# PiPod_Rev3.net
KiCad netlist of a schematic drawn in EAGLE
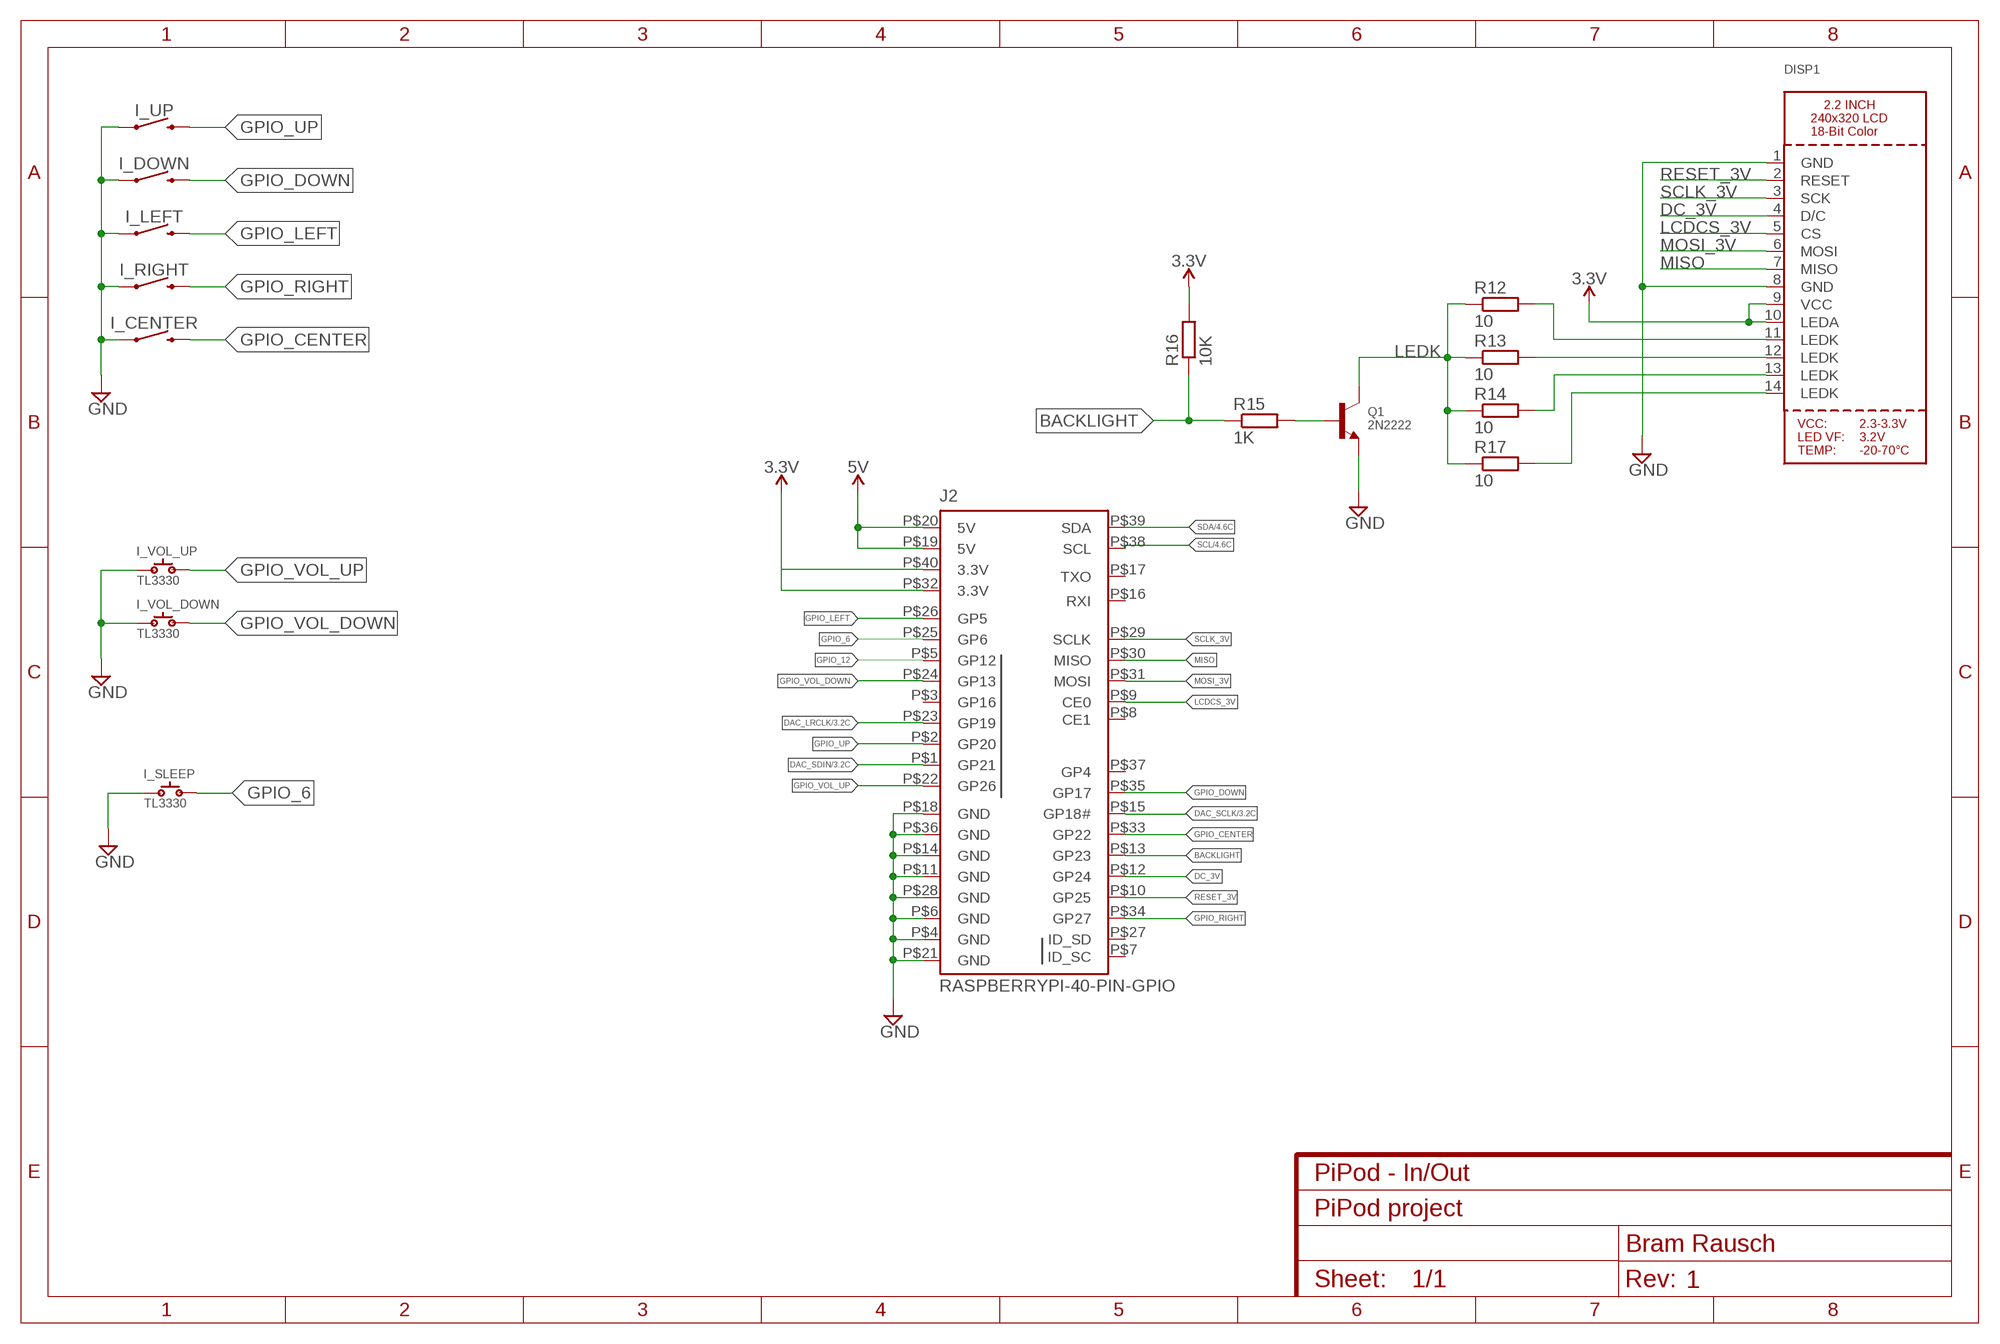
[diagram p0: schematic, sheet 1]
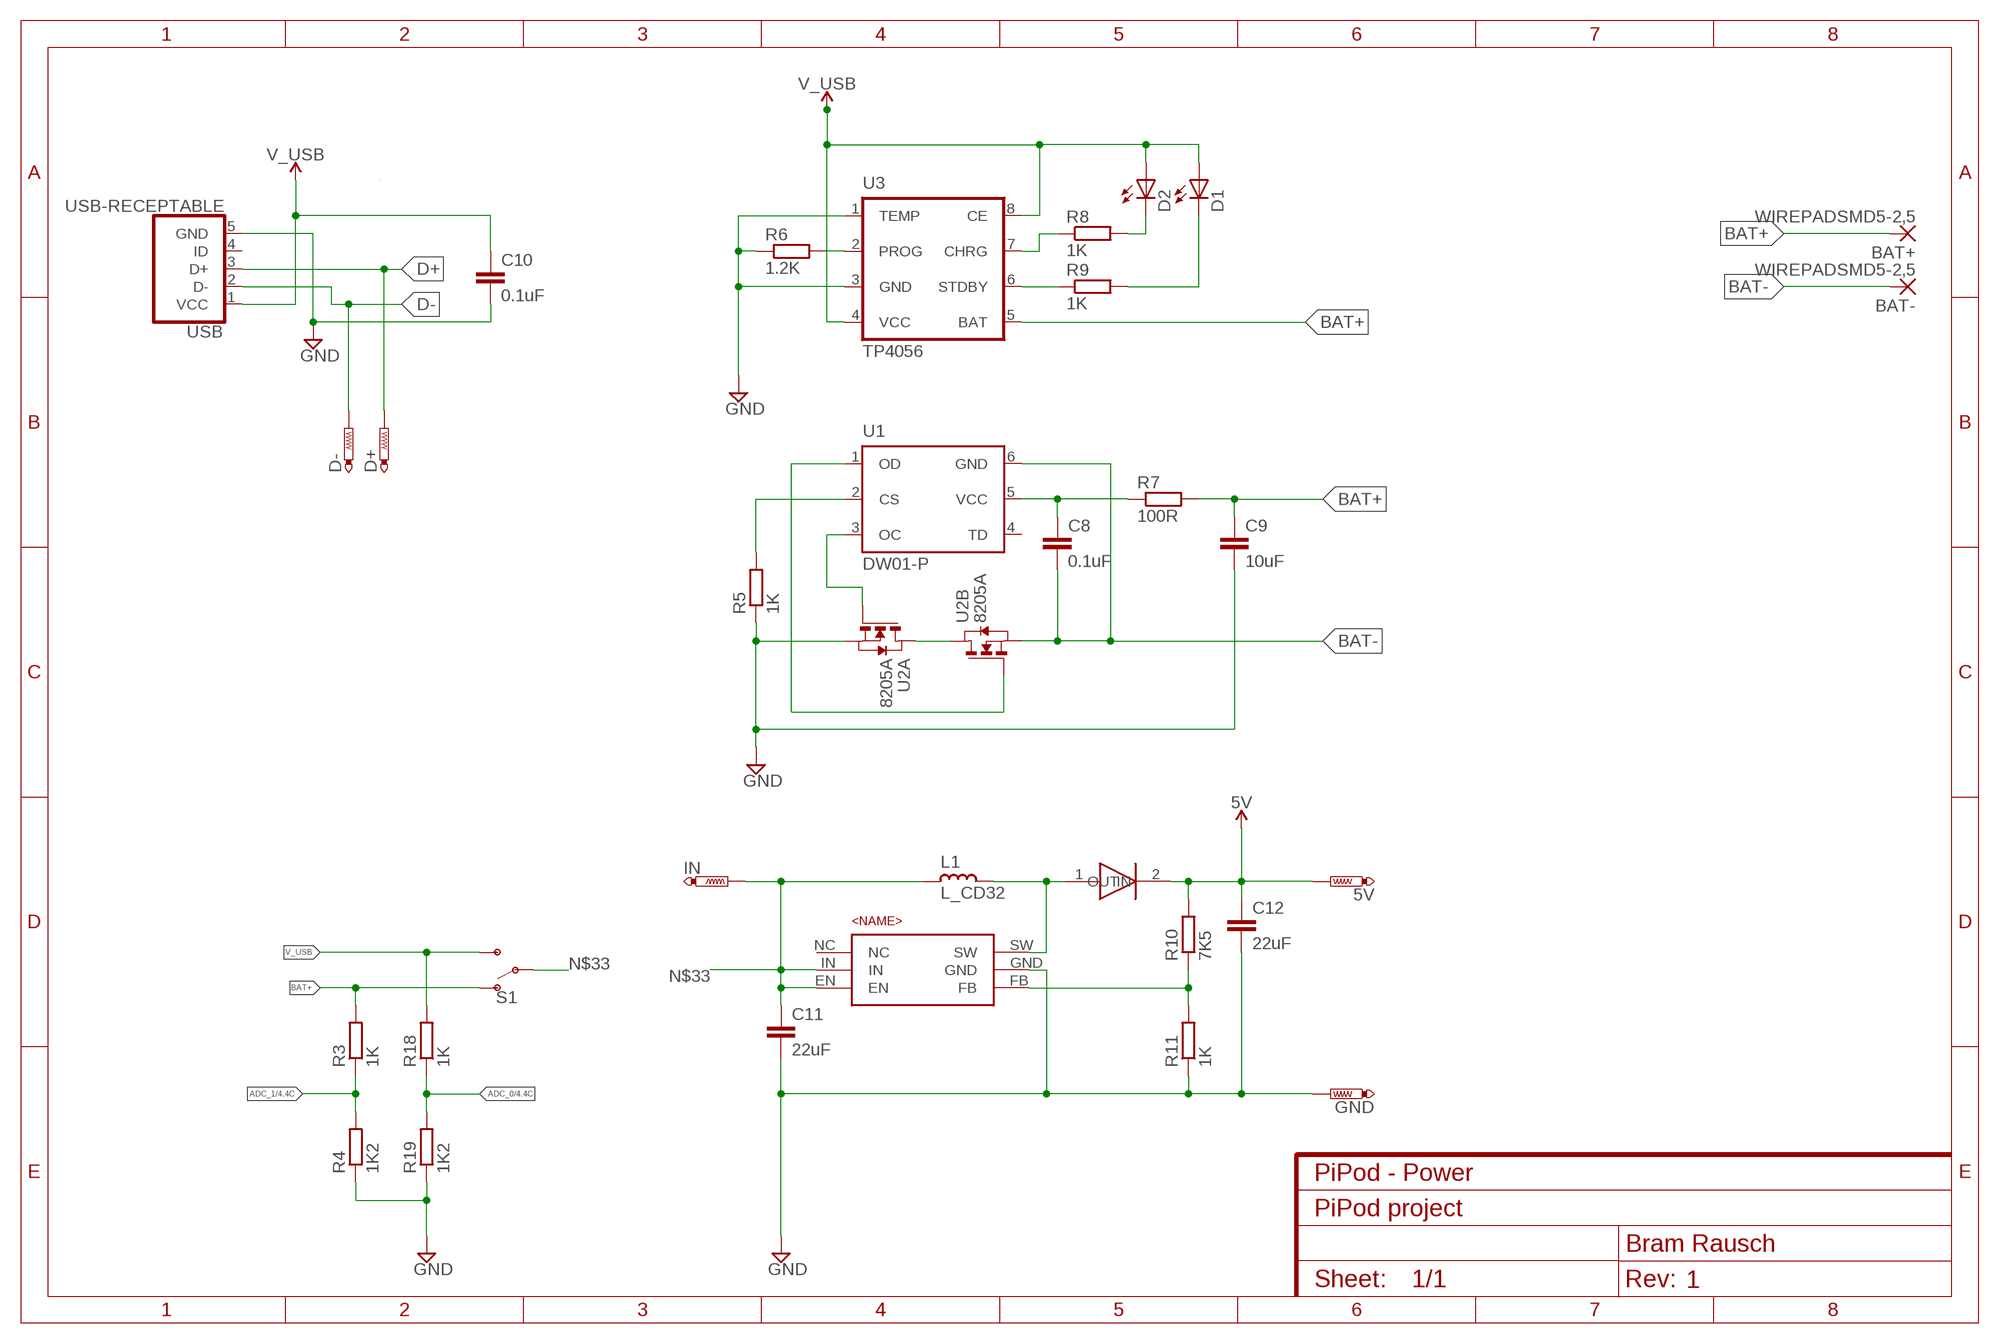
[diagram p1: schematic, sheet 2]
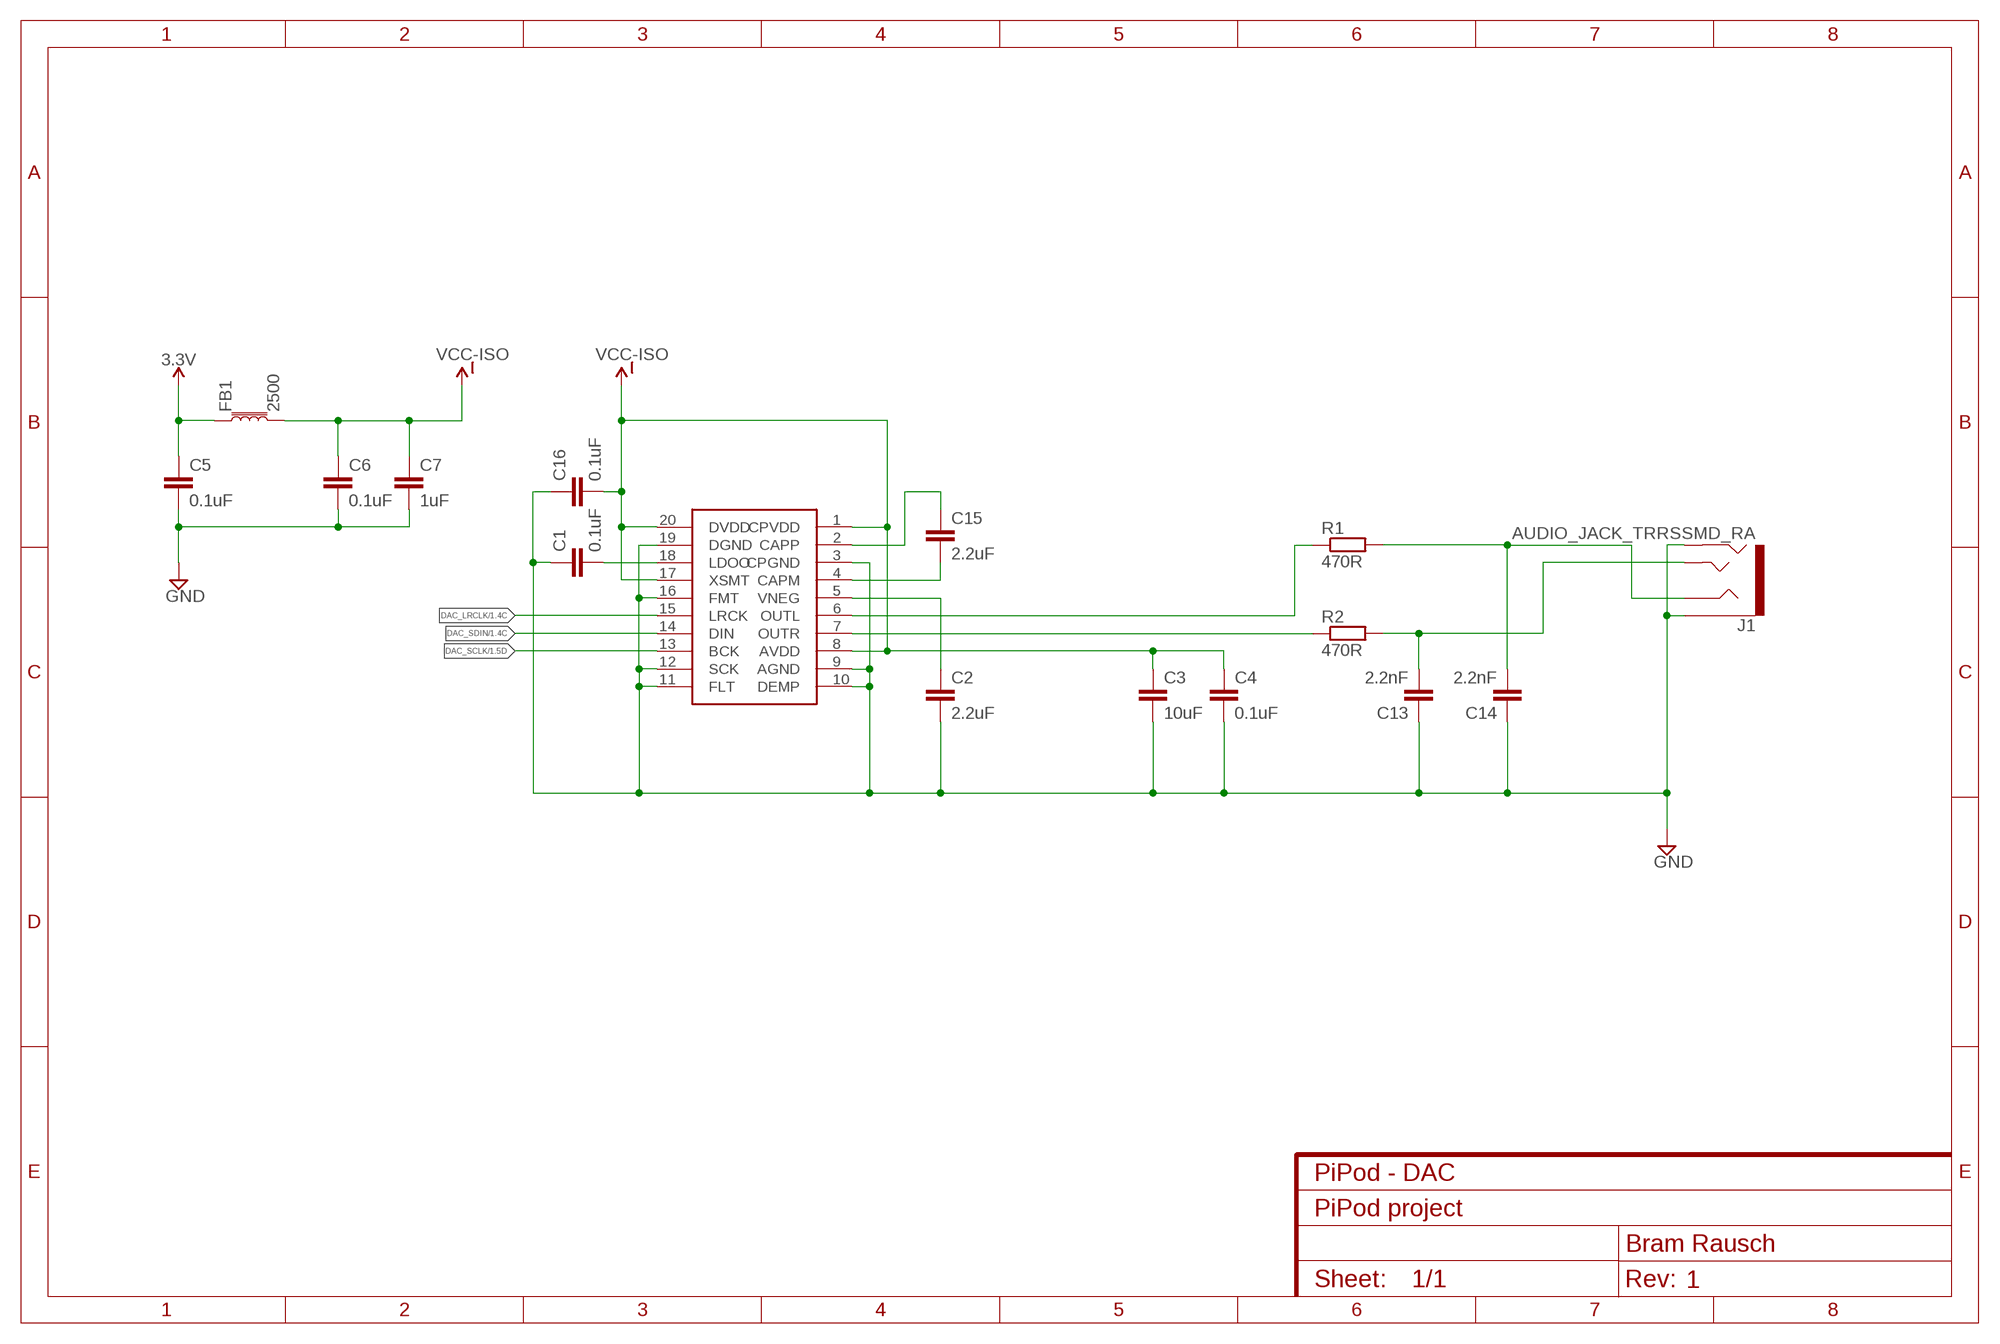
[diagram p2: schematic, sheet 3]
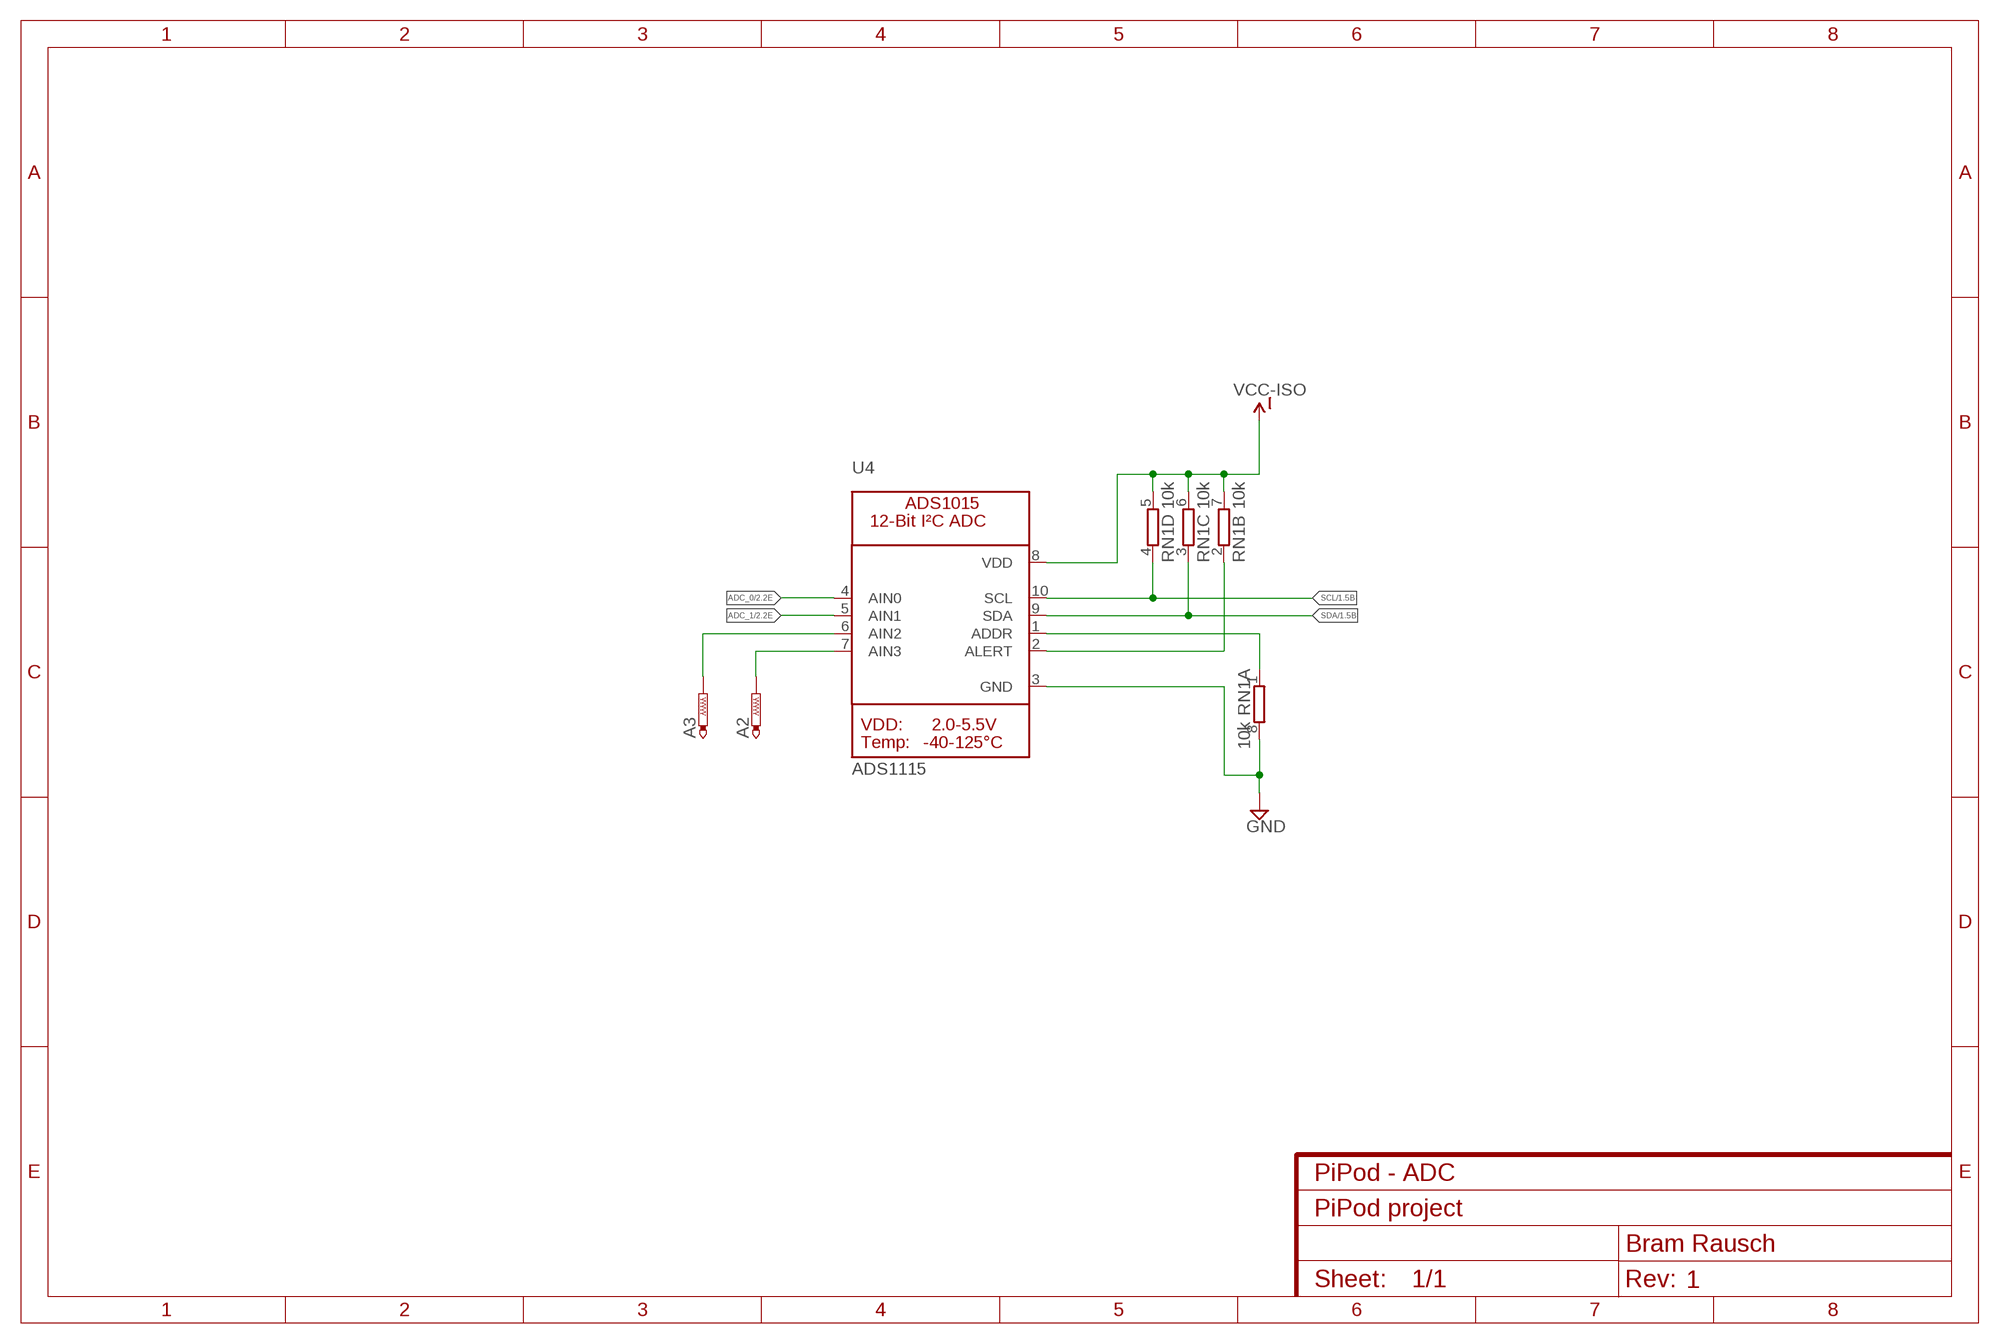
[diagram p3: schematic, sheet 4]

(export (version "E")
  (design (tool "Eeschema 10.0.6"))
  (components
    (comp (ref "DISP1")
      (value "DISP_LCD_TM022HDH26")
      (footprint "eagle-import:TM022HDH26_2.2IN_LCD")
      (libsource (lib "eagle-import") (part "DISP_LCD_TM022HDH26"))
    )
    (comp (ref "I_CENTER")
      (value "MOMENTARY-SWITCH-SPST-SMD-5.2-REDUNDANT")
      (footprint "eagle-import:TACTILE_SWITCH_SMD_5.2MM")
      (libsource (lib "eagle-import") (part "MOMENTARY-SWITCH-SPST-SMD-5.2-REDUNDANT"))
    )
    (comp (ref "I_DOWN")
      (value "MOMENTARY-SWITCH-SPST-SMD-5.2-REDUNDANT")
      (footprint "eagle-import:TACTILE_SWITCH_SMD_5.2MM")
      (libsource (lib "eagle-import") (part "MOMENTARY-SWITCH-SPST-SMD-5.2-REDUNDANT"))
    )
    (comp (ref "I_LEFT")
      (value "MOMENTARY-SWITCH-SPST-SMD-5.2-REDUNDANT")
      (footprint "eagle-import:TACTILE_SWITCH_SMD_5.2MM")
      (libsource (lib "eagle-import") (part "MOMENTARY-SWITCH-SPST-SMD-5.2-REDUNDANT"))
    )
    (comp (ref "I_RIGHT")
      (value "MOMENTARY-SWITCH-SPST-SMD-5.2-REDUNDANT")
      (footprint "eagle-import:TACTILE_SWITCH_SMD_5.2MM")
      (libsource (lib "eagle-import") (part "MOMENTARY-SWITCH-SPST-SMD-5.2-REDUNDANT"))
    )
    (comp (ref "I_SLEEP")
      (value "TL3330")
      (footprint "eagle-import:TL3330")
      (libsource (lib "eagle-import") (part "TL3330"))
    )
    (comp (ref "I_UP")
      (value "MOMENTARY-SWITCH-SPST-SMD-5.2-REDUNDANT")
      (footprint "eagle-import:TACTILE_SWITCH_SMD_5.2MM")
      (libsource (lib "eagle-import") (part "MOMENTARY-SWITCH-SPST-SMD-5.2-REDUNDANT"))
    )
    (comp (ref "I_VOL_DOWN")
      (value "TL3330")
      (footprint "eagle-import:TL3330")
      (libsource (lib "eagle-import") (part "TL3330"))
    )
    (comp (ref "I_VOL_UP")
      (value "TL3330")
      (footprint "eagle-import:TL3330")
      (libsource (lib "eagle-import") (part "TL3330"))
    )
    (comp (ref "J2")
      (value "RASPBERRYPI-40-PIN-GPIO")
      (footprint "eagle-import:2X20_SMD")
      (libsource (lib "eagle-import") (part "RASPBERRYPI-40-PIN-GPIO"))
    )
    (comp (ref "Q1")
      (value "2N2222")
      (footprint "eagle-import:SOT23-WIDE")
      (libsource (lib "eagle-import") (part "TRANSISTOR_NPNWIDE"))
    )
    (comp (ref "R12")
      (value "10")
      (footprint "eagle-import:R0805")
      (libsource (lib "eagle-import") (part "R-EU_R0805"))
    )
    (comp (ref "R13")
      (value "10")
      (footprint "eagle-import:R0805")
      (libsource (lib "eagle-import") (part "R-EU_R0805"))
    )
    (comp (ref "R14")
      (value "10")
      (footprint "eagle-import:R0805")
      (libsource (lib "eagle-import") (part "R-EU_R0805"))
    )
    (comp (ref "R15")
      (value "1K")
      (footprint "eagle-import:R0805")
      (libsource (lib "eagle-import") (part "R-EU_R0805"))
    )
    (comp (ref "R16")
      (value "10K")
      (footprint "eagle-import:R0805")
      (libsource (lib "eagle-import") (part "R-EU_R0805"))
    )
    (comp (ref "R17")
      (value "10")
      (footprint "eagle-import:R0805")
      (libsource (lib "eagle-import") (part "R-EU_R0805"))
    )
    (comp (ref "C1")
      (value "0.1uF")
      (footprint "eagle-import:C0805K")
      (libsource (lib "eagle-import") (part "C-EUC0805K"))
    )
    (comp (ref "C2")
      (value "2.2uF")
      (footprint "eagle-import:C0805K")
      (libsource (lib "eagle-import") (part "C-EUC0805K"))
    )
    (comp (ref "C3")
      (value "10uF")
      (footprint "eagle-import:C0805K")
      (libsource (lib "eagle-import") (part "C-EUC0805K"))
    )
    (comp (ref "C4")
      (value "0.1uF")
      (footprint "eagle-import:C0805K")
      (libsource (lib "eagle-import") (part "C-EUC0805K"))
    )
    (comp (ref "C5")
      (value "0.1uF")
      (footprint "eagle-import:C0805K")
      (libsource (lib "eagle-import") (part "C-EUC0805K"))
    )
    (comp (ref "C6")
      (value "0.1uF")
      (footprint "eagle-import:C0805K")
      (libsource (lib "eagle-import") (part "C-EUC0805K"))
    )
    (comp (ref "C7")
      (value "1uF")
      (footprint "eagle-import:C0805K")
      (libsource (lib "eagle-import") (part "C-EUC0805K"))
    )
    (comp (ref "C13")
      (value "2.2nF")
      (footprint "eagle-import:C0805K")
      (libsource (lib "eagle-import") (part "C-EUC0805K"))
    )
    (comp (ref "C14")
      (value "2.2nF")
      (footprint "eagle-import:C0805K")
      (libsource (lib "eagle-import") (part "C-EUC0805K"))
    )
    (comp (ref "C15")
      (value "2.2uF")
      (footprint "eagle-import:C0805K")
      (libsource (lib "eagle-import") (part "C-EUC0805K"))
    )
    (comp (ref "C16")
      (value "0.1uF")
      (footprint "eagle-import:C0805K")
      (libsource (lib "eagle-import") (part "C-EUC0805K"))
    )
    (comp (ref "FB1")
      (value "2500")
      (footprint "eagle-import:0603")
      (libsource (lib "eagle-import") (part "FERRITE_BEAD-0603"))
    )
    (comp (ref "J1")
      (value "AUDIO_JACK_TRRSSMD_RA")
      (footprint "eagle-import:AUDIO_JACK_3.5MM_TRRS_SMD_RA")
      (libsource (lib "eagle-import") (part "AUDIO_JACK_TRRSSMD_RA"))
    )
    (comp (ref "R1")
      (value "470R")
      (footprint "eagle-import:R0805")
      (libsource (lib "eagle-import") (part "R-EU_R0805"))
    )
    (comp (ref "R2")
      (value "470R")
      (footprint "eagle-import:R0805")
      (libsource (lib "eagle-import") (part "R-EU_R0805"))
    )
    (comp (ref "U5")
      (value "PCM5102")
      (footprint "eagle-import:TSSOP20")
      (libsource (lib "eagle-import") (part "PCM5102"))
    )
    (comp (ref "5V")
      (value "PTR1B2,54")
      (footprint "eagle-import:B2,54")
      (libsource (lib "eagle-import") (part "PTR1B2,54"))
    )
    (comp (ref "BAT+")
      (value "WIREPADSMD5-2,5")
      (footprint "eagle-import:5-2,5")
      (libsource (lib "eagle-import") (part "WIREPADSMD5-2,5"))
    )
    (comp (ref "BAT-")
      (value "WIREPADSMD5-2,5")
      (footprint "eagle-import:5-2,5")
      (libsource (lib "eagle-import") (part "WIREPADSMD5-2,5"))
    )
    (comp (ref "C8")
      (value "0.1uF")
      (footprint "eagle-import:C1206K")
      (libsource (lib "eagle-import") (part "resistor_348_C-EUC1206K"))
    )
    (comp (ref "C9")
      (value "10uF")
      (footprint "eagle-import:C1206K")
      (libsource (lib "eagle-import") (part "resistor_348_C-EUC1206K"))
    )
    (comp (ref "C10")
      (value "0.1uF")
      (footprint "eagle-import:C1206K")
      (libsource (lib "eagle-import") (part "resistor_348_C-EUC1206K"))
    )
    (comp (ref "C11")
      (value "22uF")
      (footprint "eagle-import:C0805K")
      (libsource (lib "eagle-import") (part "resistor_348_C-EUC0805K"))
    )
    (comp (ref "C12")
      (value "22uF")
      (footprint "eagle-import:C0805K")
      (libsource (lib "eagle-import") (part "resistor_348_C-EUC0805K"))
    )
    (comp (ref "D+")
      (value "PTR1TP15R")
      (footprint "eagle-import:TP15R")
      (libsource (lib "eagle-import") (part "PTR1TP15R"))
    )
    (comp (ref "D-")
      (value "PTR1TP15R")
      (footprint "eagle-import:TP15R")
      (libsource (lib "eagle-import") (part "PTR1TP15R"))
    )
    (comp (ref "D1")
      (value "LEDCHIPLED_0805")
      (footprint "eagle-import:CHIPLED_0805")
      (libsource (lib "eagle-import") (part "LEDCHIPLED_0805"))
    )
    (comp (ref "D2")
      (value "LEDCHIPLED_0805")
      (footprint "eagle-import:CHIPLED_0805")
      (libsource (lib "eagle-import") (part "LEDCHIPLED_0805"))
    )
    (comp (ref "GND")
      (value "PTR1B2,54")
      (footprint "eagle-import:B2,54")
      (libsource (lib "eagle-import") (part "PTR1B2,54"))
    )
    (comp (ref "IN")
      (value "PTR1B2,54")
      (footprint "eagle-import:B2,54")
      (libsource (lib "eagle-import") (part "PTR1B2,54"))
    )
    (comp (ref "L1")
      (value "L_CD32")
      (footprint "eagle-import:CD32")
      (libsource (lib "eagle-import") (part "L_CD32"))
    )
    (comp (ref "R3")
      (value "1K")
      (footprint "eagle-import:R0805")
      (libsource (lib "eagle-import") (part "R-EU_R0805"))
    )
    (comp (ref "R4")
      (value "1K2")
      (footprint "eagle-import:R0805")
      (libsource (lib "eagle-import") (part "R-EU_R0805"))
    )
    (comp (ref "R5")
      (value "1K")
      (footprint "eagle-import:M0805")
      (libsource (lib "eagle-import") (part "R-EU_M0805"))
    )
    (comp (ref "R6")
      (value "1.2K")
      (footprint "eagle-import:M0805")
      (libsource (lib "eagle-import") (part "R-EU_M0805"))
    )
    (comp (ref "R7")
      (value "100R")
      (footprint "eagle-import:M0805")
      (libsource (lib "eagle-import") (part "R-EU_M0805"))
    )
    (comp (ref "R8")
      (value "1K")
      (footprint "eagle-import:M0805")
      (libsource (lib "eagle-import") (part "R-EU_M0805"))
    )
    (comp (ref "R9")
      (value "1K")
      (footprint "eagle-import:M0805")
      (libsource (lib "eagle-import") (part "R-EU_M0805"))
    )
    (comp (ref "R10")
      (value "7K5")
      (footprint "eagle-import:R0805")
      (libsource (lib "eagle-import") (part "R-EU_R0805"))
    )
    (comp (ref "R11")
      (value "1K")
      (footprint "eagle-import:R0805")
      (libsource (lib "eagle-import") (part "R-EU_R0805"))
    )
    (comp (ref "R18")
      (value "1K")
      (footprint "eagle-import:R0805")
      (libsource (lib "eagle-import") (part "R-EU_R0805"))
    )
    (comp (ref "R19")
      (value "1K2")
      (footprint "eagle-import:R0805")
      (libsource (lib "eagle-import") (part "R-EU_R0805"))
    )
    (comp (ref "S1")
      (value "SWITCH-SPDT-PTH-11.6X4.0MM")
      (footprint "eagle-import:SWITCH_SPDT_PTH_11.6X4.0MM")
      (libsource (lib "eagle-import") (part "SWITCH-SPDT-PTH-11.6X4.0MM"))
    )
    (comp (ref "U$9")
      (value "SMA-SS34")
      (footprint "eagle-import:SMA-SS34")
      (libsource (lib "eagle-import") (part "SMA-SS34"))
    )
    (comp (ref "U1")
      (value "DW01-P")
      (footprint "eagle-import:SOT23-6L")
      (libsource (lib "eagle-import") (part "DW01-P"))
    )
    (comp (ref "U2")
      (value "8205A")
      (footprint "eagle-import:TSSOP8")
      (libsource (lib "eagle-import") (part "8205A"))
    )
    (comp (ref "U3")
      (value "TP4056")
      (footprint "eagle-import:SO08")
      (libsource (lib "eagle-import") (part "TP4056"))
    )
    (comp (ref "U6")
      (value "MT3608")
      (footprint "eagle-import:SOT23-6")
      (libsource (lib "eagle-import") (part "MT3608"))
    )
    (comp (ref "USB")
      (value "USB-RECEPTABLE")
      (footprint "eagle-import:FCI-10103594-0001LF")
      (libsource (lib "eagle-import") (part "USB-RECEPTABLE"))
    )
    (comp (ref "A2")
      (value "PTR1TP15R")
      (footprint "eagle-import:TP15R")
      (libsource (lib "eagle-import") (part "PTR1TP15R"))
    )
    (comp (ref "A3")
      (value "PTR1TP15R")
      (footprint "eagle-import:TP15R")
      (libsource (lib "eagle-import") (part "PTR1TP15R"))
    )
    (comp (ref "RN1")
      (value "10k")
      (footprint "eagle-import:0603-ARC")
      (libsource (lib "eagle-import") (part "4R-N0603-ARC"))
    )
    (comp (ref "U4")
      (value "ADS1115")
      (footprint "eagle-import:MICROBUILDER_MSOP10")
      (libsource (lib "eagle-import") (part "MICROBUILDER_ADC_ADS1015"))
    )
  )
  (nets
    (net (code "1") (name "3.3V") (class "Default")
      (node (ref "C5") (pin "1") (pinfunction "1_1") (pintype "passive"))
      (node (ref "DISP1") (pin "10") (pinfunction "LEDA_10") (pintype "power_in"))
      (node (ref "DISP1") (pin "9") (pinfunction "VCC_9") (pintype "power_in"))
      (node (ref "FB1") (pin "1") (pinfunction "1_1") (pintype "passive"))
      (node (ref "J2") (pin "P$32") (pinfunction "3.3V_P$32") (pintype "power_in"))
      (node (ref "J2") (pin "P$40") (pinfunction "3.3V_P$40") (pintype "power_in"))
      (node (ref "R16") (pin "2") (pinfunction "2_2") (pintype "passive"))
    )
    (net (code "2") (name "5V") (class "Default")
      (node (ref "5V") (pin "TP") (pinfunction "TP_TP") (pintype "input"))
      (node (ref "C12") (pin "1") (pinfunction "1_1") (pintype "passive"))
      (node (ref "J2") (pin "P$19") (pinfunction "5V_P$19") (pintype "power_in"))
      (node (ref "J2") (pin "P$20") (pinfunction "5V_P$20") (pintype "power_in"))
      (node (ref "R10") (pin "2") (pinfunction "2_2") (pintype "passive"))
      (node (ref "U$9") (pin "2") (pinfunction "OUT_2") (pintype "bidirectional"))
    )
    (net (code "3") (name "ADC_0") (class "Default")
      (node (ref "R18") (pin "1") (pinfunction "1_1") (pintype "passive"))
      (node (ref "R19") (pin "2") (pinfunction "2_2") (pintype "passive"))
      (node (ref "U4") (pin "4") (pinfunction "AIN0_4") (pintype "bidirectional"))
    )
    (net (code "4") (name "ADC_1") (class "Default")
      (node (ref "R3") (pin "1") (pinfunction "1_1") (pintype "passive"))
      (node (ref "R4") (pin "2") (pinfunction "2_2") (pintype "passive"))
      (node (ref "U4") (pin "5") (pinfunction "AIN1_5") (pintype "bidirectional"))
    )
    (net (code "5") (name "BACKLIGHT") (class "Default")
      (node (ref "J2") (pin "P$13") (pinfunction "GP23_P$13") (pintype "bidirectional"))
      (node (ref "R15") (pin "1") (pinfunction "1_1") (pintype "passive"))
      (node (ref "R16") (pin "1") (pinfunction "1_1") (pintype "passive"))
    )
    (net (code "6") (name "BAT+") (class "Default")
      (node (ref "BAT+") (pin "1") (pinfunction "P_1") (pintype "passive"))
      (node (ref "C9") (pin "1") (pinfunction "1_1") (pintype "passive"))
      (node (ref "R3") (pin "2") (pinfunction "2_2") (pintype "passive"))
      (node (ref "R7") (pin "2") (pinfunction "2_2") (pintype "passive"))
      (node (ref "S1") (pin "1") (pinfunction "O_1") (pintype "passive"))
      (node (ref "U3") (pin "5") (pinfunction "BAT_5") (pintype "input"))
    )
    (net (code "7") (name "BAT-") (class "Default")
      (node (ref "BAT-") (pin "1") (pinfunction "P_1") (pintype "passive"))
      (node (ref "C8") (pin "2") (pinfunction "2_2") (pintype "passive"))
      (node (ref "U1") (pin "6") (pinfunction "GND_6") (pintype "output"))
      (node (ref "U2") (pin "6") (pinfunction "S_6") (pintype "passive"))
      (node (ref "U2") (pin "7") (pinfunction "S_7") (pintype "passive"))
    )
    (net (code "8") (name "D+") (class "Default")
      (node (ref "D+") (pin "TP") (pinfunction "TP_TP") (pintype "input"))
      (node (ref "USB") (pin "3") (pinfunction "D+_3") (pintype "bidirectional"))
    )
    (net (code "9") (name "D-") (class "Default")
      (node (ref "D-") (pin "TP") (pinfunction "TP_TP") (pintype "input"))
      (node (ref "USB") (pin "2") (pinfunction "D-_2") (pintype "bidirectional"))
    )
    (net (code "10") (name "DAC_LRCLK") (class "Default")
      (node (ref "J2") (pin "P$23") (pinfunction "GP19_P$23") (pintype "bidirectional"))
      (node (ref "U5") (pin "15") (pinfunction "LRCK_15") (pintype "bidirectional"))
    )
    (net (code "11") (name "DAC_SCLK") (class "Default")
      (node (ref "J2") (pin "P$15") (pinfunction "GP18#_P$15") (pintype "bidirectional"))
      (node (ref "U5") (pin "13") (pinfunction "BCK_13") (pintype "bidirectional"))
    )
    (net (code "12") (name "DAC_SDIN") (class "Default")
      (node (ref "J2") (pin "P$1") (pinfunction "GP21_P$1") (pintype "bidirectional"))
      (node (ref "U5") (pin "14") (pinfunction "DIN_14") (pintype "bidirectional"))
    )
    (net (code "13") (name "DC_3V") (class "Default")
      (node (ref "DISP1") (pin "4") (pinfunction "D/C_4") (pintype "input"))
      (node (ref "J2") (pin "P$12") (pinfunction "GP24_P$12") (pintype "bidirectional"))
    )
    (net (code "14") (name "GND") (class "Default")
      (node (ref "C1") (pin "1") (pinfunction "1_1") (pintype "passive"))
      (node (ref "C10") (pin "2") (pinfunction "2_2") (pintype "passive"))
      (node (ref "C11") (pin "2") (pinfunction "2_2") (pintype "passive"))
      (node (ref "C12") (pin "2") (pinfunction "2_2") (pintype "passive"))
      (node (ref "C13") (pin "1") (pinfunction "1_1") (pintype "passive"))
      (node (ref "C14") (pin "1") (pinfunction "1_1") (pintype "passive"))
      (node (ref "C16") (pin "1") (pinfunction "1_1") (pintype "passive"))
      (node (ref "C2") (pin "2") (pinfunction "2_2") (pintype "passive"))
      (node (ref "C3") (pin "2") (pinfunction "2_2") (pintype "passive"))
      (node (ref "C4") (pin "2") (pinfunction "2_2") (pintype "passive"))
      (node (ref "C5") (pin "2") (pinfunction "2_2") (pintype "passive"))
      (node (ref "C6") (pin "2") (pinfunction "2_2") (pintype "passive"))
      (node (ref "C7") (pin "2") (pinfunction "2_2") (pintype "passive"))
      (node (ref "C9") (pin "2") (pinfunction "2_2") (pintype "passive"))
      (node (ref "DISP1") (pin "1") (pinfunction "GND_1") (pintype "power_in"))
      (node (ref "DISP1") (pin "8") (pinfunction "GND_8") (pintype "power_in"))
      (node (ref "GND") (pin "TP") (pinfunction "TP_TP") (pintype "input"))
      (node (ref "I_CENTER") (pin "1") (pinfunction "1_1") (pintype "passive"))
      (node (ref "I_CENTER") (pin "2") (pinfunction "1_2") (pintype "passive"))
      (node (ref "I_DOWN") (pin "1") (pinfunction "1_1") (pintype "passive"))
      (node (ref "I_DOWN") (pin "2") (pinfunction "1_2") (pintype "passive"))
      (node (ref "I_LEFT") (pin "1") (pinfunction "1_1") (pintype "passive"))
      (node (ref "I_LEFT") (pin "2") (pinfunction "1_2") (pintype "passive"))
      (node (ref "I_RIGHT") (pin "1") (pinfunction "1_1") (pintype "passive"))
      (node (ref "I_RIGHT") (pin "2") (pinfunction "1_2") (pintype "passive"))
      (node (ref "I_SLEEP") (pin "1") (pinfunction "1_1") (pintype "bidirectional"))
      (node (ref "I_UP") (pin "1") (pinfunction "1_1") (pintype "passive"))
      (node (ref "I_UP") (pin "2") (pinfunction "1_2") (pintype "passive"))
      (node (ref "I_VOL_DOWN") (pin "1") (pinfunction "1_1") (pintype "bidirectional"))
      (node (ref "I_VOL_UP") (pin "1") (pinfunction "1_1") (pintype "bidirectional"))
      (node (ref "J1") (pin "EARTH") (pinfunction "EARTH_EARTH") (pintype "bidirectional"))
      (node (ref "J1") (pin "RING2") (pinfunction "RING2_RING2") (pintype "bidirectional"))
      (node (ref "J2") (pin "P$11") (pinfunction "GND_P$11") (pintype "power_in"))
      (node (ref "J2") (pin "P$14") (pinfunction "GND_P$14") (pintype "power_in"))
      (node (ref "J2") (pin "P$18") (pinfunction "GND_P$18") (pintype "power_in"))
      (node (ref "J2") (pin "P$21") (pinfunction "GND_P$21") (pintype "power_in"))
      (node (ref "J2") (pin "P$28") (pinfunction "GND_P$28") (pintype "power_in"))
      (node (ref "J2") (pin "P$36") (pinfunction "GND_P$36") (pintype "power_in"))
      (node (ref "J2") (pin "P$4") (pinfunction "GND_P$4") (pintype "power_in"))
      (node (ref "J2") (pin "P$6") (pinfunction "GND_P$6") (pintype "power_in"))
      (node (ref "Q1") (pin "2") (pinfunction "E_2") (pintype "passive"))
      (node (ref "R11") (pin "1") (pinfunction "1_1") (pintype "passive"))
      (node (ref "R19") (pin "1") (pinfunction "1_1") (pintype "passive"))
      (node (ref "R4") (pin "1") (pinfunction "1_1") (pintype "passive"))
      (node (ref "R5") (pin "1") (pinfunction "1_1") (pintype "passive"))
      (node (ref "R6") (pin "1") (pinfunction "1_1") (pintype "passive"))
      (node (ref "RN1") (pin "8") (pinfunction "2_8") (pintype "passive"))
      (node (ref "U2") (pin "2") (pinfunction "S_2") (pintype "passive"))
      (node (ref "U2") (pin "3") (pinfunction "S_3") (pintype "passive"))
      (node (ref "U3") (pin "1") (pinfunction "TEMP_1") (pintype "power_in"))
      (node (ref "U3") (pin "3") (pinfunction "GND_3") (pintype "output"))
      (node (ref "U4") (pin "3") (pinfunction "GND_3") (pintype "bidirectional"))
      (node (ref "U5") (pin "10") (pinfunction "DEMP_10") (pintype "bidirectional"))
      (node (ref "U5") (pin "11") (pinfunction "FLT_11") (pintype "bidirectional"))
      (node (ref "U5") (pin "12") (pinfunction "SCK_12") (pintype "bidirectional"))
      (node (ref "U5") (pin "16") (pinfunction "FMT_16") (pintype "bidirectional"))
      (node (ref "U5") (pin "19") (pinfunction "DGND_19") (pintype "bidirectional"))
      (node (ref "U5") (pin "3") (pinfunction "CPGND_3") (pintype "bidirectional"))
      (node (ref "U5") (pin "9") (pinfunction "AGND_9") (pintype "bidirectional"))
      (node (ref "U6") (pin "GND") (pinfunction "GND_GND") (pintype "bidirectional"))
      (node (ref "USB") (pin "5") (pinfunction "GND_5") (pintype "bidirectional"))
    )
    (net (code "15") (name "GPIO_6") (class "Default")
      (node (ref "I_SLEEP") (pin "2") (pinfunction "2_2") (pintype "bidirectional"))
      (node (ref "J2") (pin "P$25") (pinfunction "GP6_P$25") (pintype "bidirectional"))
    )
    (net (code "16") (name "GPIO_12") (class "Default")
      (node (ref "J2") (pin "P$5") (pinfunction "GP12_P$5") (pintype "bidirectional"))
    )
    (net (code "17") (name "GPIO_CENTER") (class "Default")
      (node (ref "I_CENTER") (pin "3") (pinfunction "2_3") (pintype "passive"))
      (node (ref "I_CENTER") (pin "4") (pinfunction "2_4") (pintype "passive"))
      (node (ref "J2") (pin "P$33") (pinfunction "GP22_P$33") (pintype "bidirectional"))
    )
    (net (code "18") (name "GPIO_DOWN") (class "Default")
      (node (ref "I_DOWN") (pin "3") (pinfunction "2_3") (pintype "passive"))
      (node (ref "I_DOWN") (pin "4") (pinfunction "2_4") (pintype "passive"))
      (node (ref "J2") (pin "P$35") (pinfunction "GP17_P$35") (pintype "bidirectional"))
    )
    (net (code "19") (name "GPIO_LEFT") (class "Default")
      (node (ref "I_LEFT") (pin "3") (pinfunction "2_3") (pintype "passive"))
      (node (ref "I_LEFT") (pin "4") (pinfunction "2_4") (pintype "passive"))
      (node (ref "J2") (pin "P$26") (pinfunction "GP5_P$26") (pintype "bidirectional"))
    )
    (net (code "20") (name "GPIO_RIGHT") (class "Default")
      (node (ref "I_RIGHT") (pin "3") (pinfunction "2_3") (pintype "passive"))
      (node (ref "I_RIGHT") (pin "4") (pinfunction "2_4") (pintype "passive"))
      (node (ref "J2") (pin "P$34") (pinfunction "GP27_P$34") (pintype "bidirectional"))
    )
    (net (code "21") (name "GPIO_UP") (class "Default")
      (node (ref "I_UP") (pin "3") (pinfunction "2_3") (pintype "passive"))
      (node (ref "I_UP") (pin "4") (pinfunction "2_4") (pintype "passive"))
      (node (ref "J2") (pin "P$2") (pinfunction "GP20_P$2") (pintype "bidirectional"))
    )
    (net (code "22") (name "GPIO_VOL_DOWN") (class "Default")
      (node (ref "I_VOL_DOWN") (pin "2") (pinfunction "2_2") (pintype "bidirectional"))
      (node (ref "J2") (pin "P$24") (pinfunction "GP13_P$24") (pintype "bidirectional"))
    )
    (net (code "23") (name "GPIO_VOL_UP") (class "Default")
      (node (ref "I_VOL_UP") (pin "2") (pinfunction "2_2") (pintype "bidirectional"))
      (node (ref "J2") (pin "P$22") (pinfunction "GP26_P$22") (pintype "bidirectional"))
    )
    (net (code "24") (name "LCDCS_3V") (class "Default")
      (node (ref "DISP1") (pin "5") (pinfunction "CS_5") (pintype "input"))
      (node (ref "J2") (pin "P$9") (pinfunction "CE0_P$9") (pintype "output"))
    )
    (net (code "25") (name "LEDK") (class "Default")
      (node (ref "Q1") (pin "3") (pinfunction "C_3") (pintype "passive"))
      (node (ref "R12") (pin "1") (pinfunction "1_1") (pintype "passive"))
      (node (ref "R13") (pin "1") (pinfunction "1_1") (pintype "passive"))
      (node (ref "R14") (pin "1") (pinfunction "1_1") (pintype "passive"))
      (node (ref "R17") (pin "1") (pinfunction "1_1") (pintype "passive"))
    )
    (net (code "26") (name "MISO") (class "Default")
      (node (ref "DISP1") (pin "7") (pinfunction "MISO_7") (pintype "output"))
      (node (ref "J2") (pin "P$30") (pinfunction "MISO_P$30") (pintype "input"))
    )
    (net (code "27") (name "MOSI_3V") (class "Default")
      (node (ref "DISP1") (pin "6") (pinfunction "MOSI_6") (pintype "input"))
      (node (ref "J2") (pin "P$31") (pinfunction "MOSI_P$31") (pintype "output"))
    )
    (net (code "28") (name "N$33") (class "Default")
      (node (ref "C11") (pin "1") (pinfunction "1_1") (pintype "passive"))
      (node (ref "IN") (pin "TP") (pinfunction "TP_TP") (pintype "input"))
      (node (ref "L1") (pin "2") (pinfunction "2_2") (pintype "passive"))
      (node (ref "S1") (pin "2") (pinfunction "P_2") (pintype "passive"))
      (node (ref "U6") (pin "EN") (pinfunction "EN_EN") (pintype "bidirectional"))
      (node (ref "U6") (pin "IN") (pinfunction "IN_IN") (pintype "bidirectional"))
    )
    (net (code "29") (name "Net-(C13-Pad2)") (class "Default")
      (node (ref "C13") (pin "2") (pinfunction "2_2") (pintype "passive"))
      (node (ref "J1") (pin "TIP") (pinfunction "TIP_TIP") (pintype "bidirectional"))
      (node (ref "R2") (pin "2") (pinfunction "2_2") (pintype "passive"))
    )
    (net (code "30") (name "Net-(C14-Pad2)") (class "Default")
      (node (ref "C14") (pin "2") (pinfunction "2_2") (pintype "passive"))
      (node (ref "J1") (pin "RING1") (pinfunction "RING1_RING1") (pintype "bidirectional"))
      (node (ref "R1") (pin "2") (pinfunction "2_2") (pintype "passive"))
    )
    (net (code "31") (name "Net-(D1-PadC)") (class "Default")
      (node (ref "D1") (pin "C") (pinfunction "C_C") (pintype "passive"))
      (node (ref "R9") (pin "2") (pinfunction "2_2") (pintype "passive"))
    )
    (net (code "32") (name "Net-(D2-PadC)") (class "Default")
      (node (ref "D2") (pin "C") (pinfunction "C_C") (pintype "passive"))
      (node (ref "R8") (pin "2") (pinfunction "2_2") (pintype "passive"))
    )
    (net (code "33") (name "Net-(DISP1-LEDK-Pad11)") (class "Default")
      (node (ref "DISP1") (pin "11") (pinfunction "LEDK_11") (pintype "power_in"))
      (node (ref "R12") (pin "2") (pinfunction "2_2") (pintype "passive"))
    )
    (net (code "34") (name "Net-(DISP1-LEDK-Pad12)") (class "Default")
      (node (ref "DISP1") (pin "12") (pinfunction "LEDK_12") (pintype "power_in"))
      (node (ref "R13") (pin "2") (pinfunction "2_2") (pintype "passive"))
    )
    (net (code "35") (name "Net-(DISP1-LEDK-Pad13)") (class "Default")
      (node (ref "DISP1") (pin "13") (pinfunction "LEDK_13") (pintype "power_in"))
      (node (ref "R14") (pin "2") (pinfunction "2_2") (pintype "passive"))
    )
    (net (code "36") (name "Net-(DISP1-LEDK-Pad14)") (class "Default")
      (node (ref "DISP1") (pin "14") (pinfunction "LEDK_14") (pintype "power_in"))
      (node (ref "R17") (pin "2") (pinfunction "2_2") (pintype "passive"))
    )
    (net (code "37") (name "Net-(Q1-B)") (class "Default")
      (node (ref "Q1") (pin "1") (pinfunction "B_1") (pintype "passive"))
      (node (ref "R15") (pin "2") (pinfunction "2_2") (pintype "passive"))
    )
    (net (code "38") (name "Net-(R10-Pad1)") (class "Default")
      (node (ref "R10") (pin "1") (pinfunction "1_1") (pintype "passive"))
      (node (ref "R11") (pin "2") (pinfunction "2_2") (pintype "passive"))
      (node (ref "U6") (pin "FB") (pinfunction "FB_FB") (pintype "bidirectional"))
    )
    (net (code "39") (name "Net-(RN1B-1)") (class "Default")
      (node (ref "RN1") (pin "2") (pinfunction "1_2") (pintype "passive"))
      (node (ref "U4") (pin "2") (pinfunction "ALERT_2") (pintype "bidirectional"))
    )
    (net (code "40") (name "Net-(U$9-IN)") (class "Default")
      (node (ref "L1") (pin "1") (pinfunction "1_1") (pintype "passive"))
      (node (ref "U$9") (pin "1") (pinfunction "IN_1") (pintype "input"))
      (node (ref "U6") (pin "SW") (pinfunction "SW_SW") (pintype "bidirectional"))
    )
    (net (code "41") (name "Net-(U1-CS)") (class "Default")
      (node (ref "R5") (pin "2") (pinfunction "2_2") (pintype "passive"))
      (node (ref "U1") (pin "2") (pinfunction "CS_2") (pintype "input"))
    )
    (net (code "42") (name "Net-(U1-OC)") (class "Default")
      (node (ref "U1") (pin "3") (pinfunction "OC_3") (pintype "power_in"))
      (node (ref "U2") (pin "4") (pinfunction "G_4") (pintype "passive"))
    )
    (net (code "43") (name "Net-(U1-OD)") (class "Default")
      (node (ref "U1") (pin "1") (pinfunction "OD_1") (pintype "power_in"))
      (node (ref "U2") (pin "5") (pinfunction "G_5") (pintype "passive"))
    )
    (net (code "44") (name "Net-(U1-VCC)") (class "Default")
      (node (ref "C8") (pin "1") (pinfunction "1_1") (pintype "passive"))
      (node (ref "R7") (pin "1") (pinfunction "1_1") (pintype "passive"))
      (node (ref "U1") (pin "5") (pinfunction "VCC_5") (pintype "input"))
    )
    (net (code "45") (name "Net-(U2A-D)") (class "Default")
      (node (ref "U2") (pin "1") (pinfunction "D_1") (pintype "passive"))
      (node (ref "U2") (pin "8") (pinfunction "D_8") (pintype "passive"))
    )
    (net (code "46") (name "Net-(U3-CHRG)") (class "Default")
      (node (ref "R8") (pin "1") (pinfunction "1_1") (pintype "passive"))
      (node (ref "U3") (pin "7") (pinfunction "CHRG_7") (pintype "output"))
    )
    (net (code "47") (name "Net-(U3-PROG)") (class "Default")
      (node (ref "R6") (pin "2") (pinfunction "2_2") (pintype "passive"))
      (node (ref "U3") (pin "2") (pinfunction "PROG_2") (pintype "input"))
    )
    (net (code "48") (name "Net-(U3-STDBY)") (class "Default")
      (node (ref "R9") (pin "1") (pinfunction "1_1") (pintype "passive"))
      (node (ref "U3") (pin "6") (pinfunction "STDBY_6") (pintype "input"))
    )
    (net (code "49") (name "Net-(U4-ADDR)") (class "Default")
      (node (ref "RN1") (pin "1") (pinfunction "1_1") (pintype "passive"))
      (node (ref "U4") (pin "1") (pinfunction "ADDR_1") (pintype "bidirectional"))
    )
    (net (code "50") (name "Net-(U4-AIN2)") (class "Default")
      (node (ref "A3") (pin "TP") (pinfunction "TP_TP") (pintype "input"))
      (node (ref "U4") (pin "6") (pinfunction "AIN2_6") (pintype "bidirectional"))
    )
    (net (code "51") (name "Net-(U4-AIN3)") (class "Default")
      (node (ref "A2") (pin "TP") (pinfunction "TP_TP") (pintype "input"))
      (node (ref "U4") (pin "7") (pinfunction "AIN3_7") (pintype "bidirectional"))
    )
    (net (code "52") (name "Net-(U5-CAPM)") (class "Default")
      (node (ref "C15") (pin "2") (pinfunction "2_2") (pintype "passive"))
      (node (ref "U5") (pin "4") (pinfunction "CAPM_4") (pintype "bidirectional"))
    )
    (net (code "53") (name "Net-(U5-CAPP)") (class "Default")
      (node (ref "C15") (pin "1") (pinfunction "1_1") (pintype "passive"))
      (node (ref "U5") (pin "2") (pinfunction "CAPP_2") (pintype "bidirectional"))
    )
    (net (code "54") (name "Net-(U5-LDOO)") (class "Default")
      (node (ref "C1") (pin "2") (pinfunction "2_2") (pintype "passive"))
      (node (ref "U5") (pin "18") (pinfunction "LDOO_18") (pintype "bidirectional"))
    )
    (net (code "55") (name "Net-(U5-OUTL)") (class "Default")
      (node (ref "R1") (pin "1") (pinfunction "1_1") (pintype "passive"))
      (node (ref "U5") (pin "6") (pinfunction "OUTL_6") (pintype "bidirectional"))
    )
    (net (code "56") (name "Net-(U5-OUTR)") (class "Default")
      (node (ref "R2") (pin "1") (pinfunction "1_1") (pintype "passive"))
      (node (ref "U5") (pin "7") (pinfunction "OUTR_7") (pintype "bidirectional"))
    )
    (net (code "57") (name "Net-(U5-VNEG)") (class "Default")
      (node (ref "C2") (pin "1") (pinfunction "1_1") (pintype "passive"))
      (node (ref "U5") (pin "5") (pinfunction "VNEG_5") (pintype "bidirectional"))
    )
    (net (code "58") (name "RESET_3V") (class "Default")
      (node (ref "DISP1") (pin "2") (pinfunction "RESET_2") (pintype "input"))
      (node (ref "J2") (pin "P$10") (pinfunction "GP25_P$10") (pintype "bidirectional"))
    )
    (net (code "59") (name "SCL") (class "Default")
      (node (ref "J2") (pin "P$38") (pinfunction "SCL_P$38") (pintype "bidirectional"))
      (node (ref "RN1") (pin "4") (pinfunction "1_4") (pintype "passive"))
      (node (ref "U4") (pin "10") (pinfunction "SCL_10") (pintype "bidirectional"))
    )
    (net (code "60") (name "SCLK_3V") (class "Default")
      (node (ref "DISP1") (pin "3") (pinfunction "SCK_3") (pintype "input"))
      (node (ref "J2") (pin "P$29") (pinfunction "SCLK_P$29") (pintype "output"))
    )
    (net (code "61") (name "SDA") (class "Default")
      (node (ref "J2") (pin "P$39") (pinfunction "SDA_P$39") (pintype "bidirectional"))
      (node (ref "RN1") (pin "3") (pinfunction "1_3") (pintype "passive"))
      (node (ref "U4") (pin "9") (pinfunction "SDA_9") (pintype "bidirectional"))
    )
    (net (code "62") (name "VCC-ISO") (class "Default")
      (node (ref "C16") (pin "2") (pinfunction "2_2") (pintype "passive"))
      (node (ref "C3") (pin "1") (pinfunction "1_1") (pintype "passive"))
      (node (ref "C4") (pin "1") (pinfunction "1_1") (pintype "passive"))
      (node (ref "C6") (pin "1") (pinfunction "1_1") (pintype "passive"))
      (node (ref "C7") (pin "1") (pinfunction "1_1") (pintype "passive"))
      (node (ref "FB1") (pin "2") (pinfunction "2_2") (pintype "passive"))
      (node (ref "RN1") (pin "5") (pinfunction "2_5") (pintype "passive"))
      (node (ref "RN1") (pin "6") (pinfunction "2_6") (pintype "passive"))
      (node (ref "RN1") (pin "7") (pinfunction "2_7") (pintype "passive"))
      (node (ref "U4") (pin "8") (pinfunction "VDD_8") (pintype "bidirectional"))
      (node (ref "U5") (pin "1") (pinfunction "CPVDD_1") (pintype "bidirectional"))
      (node (ref "U5") (pin "17") (pinfunction "XSMT_17") (pintype "bidirectional"))
      (node (ref "U5") (pin "20") (pinfunction "DVDD_20") (pintype "bidirectional"))
      (node (ref "U5") (pin "8") (pinfunction "AVDD_8") (pintype "bidirectional"))
    )
    (net (code "63") (name "V_USB") (class "Default")
      (node (ref "C10") (pin "1") (pinfunction "1_1") (pintype "passive"))
      (node (ref "D1") (pin "A") (pinfunction "A_A") (pintype "passive"))
      (node (ref "D2") (pin "A") (pinfunction "A_A") (pintype "passive"))
      (node (ref "R18") (pin "2") (pinfunction "2_2") (pintype "passive"))
      (node (ref "S1") (pin "3") (pinfunction "S_3") (pintype "passive"))
      (node (ref "U3") (pin "4") (pinfunction "VCC_4") (pintype "power_in"))
      (node (ref "U3") (pin "8") (pinfunction "CE_8") (pintype "input"))
      (node (ref "USB") (pin "1") (pinfunction "VCC_1") (pintype "bidirectional"))
    )
    (net (code "64") (name "unconnected-(J2-CE1-PadP$8)") (class "Default")
      (node (ref "J2") (pin "P$8") (pinfunction "CE1_P$8") (pintype "output"))
    )
    (net (code "65") (name "unconnected-(J2-GP4-PadP$37)") (class "Default")
      (node (ref "J2") (pin "P$37") (pinfunction "GP4_P$37") (pintype "bidirectional"))
    )
    (net (code "66") (name "unconnected-(J2-GP16-PadP$3)") (class "Default")
      (node (ref "J2") (pin "P$3") (pinfunction "GP16_P$3") (pintype "bidirectional"))
    )
    (net (code "67") (name "unconnected-(J2-ID_SC-PadP$7)") (class "Default")
      (node (ref "J2") (pin "P$7") (pinfunction "ID_SC_P$7") (pintype "bidirectional"))
    )
    (net (code "68") (name "unconnected-(J2-ID_SD-PadP$27)") (class "Default")
      (node (ref "J2") (pin "P$27") (pinfunction "ID_SD_P$27") (pintype "bidirectional"))
    )
    (net (code "69") (name "unconnected-(J2-RXI-PadP$16)") (class "Default")
      (node (ref "J2") (pin "P$16") (pinfunction "RXI_P$16") (pintype "input"))
    )
    (net (code "70") (name "unconnected-(J2-TXO-PadP$17)") (class "Default")
      (node (ref "J2") (pin "P$17") (pinfunction "TXO_P$17") (pintype "output"))
    )
    (net (code "71") (name "unconnected-(U1-TD-Pad4)") (class "Default")
      (node (ref "U1") (pin "4") (pinfunction "TD_4") (pintype "output"))
    )
    (net (code "72") (name "unconnected-(U6-PadNC)") (class "Default")
      (node (ref "U6") (pin "NC") (pinfunction "NC_NC") (pintype "bidirectional"))
    )
    (net (code "73") (name "unconnected-(USB-ID-Pad4)") (class "Default")
      (node (ref "USB") (pin "4") (pinfunction "ID_4") (pintype "bidirectional"))
    )
  )
)
